# supply1.net
KiCad netlist of a schematic drawn in Altium Designer
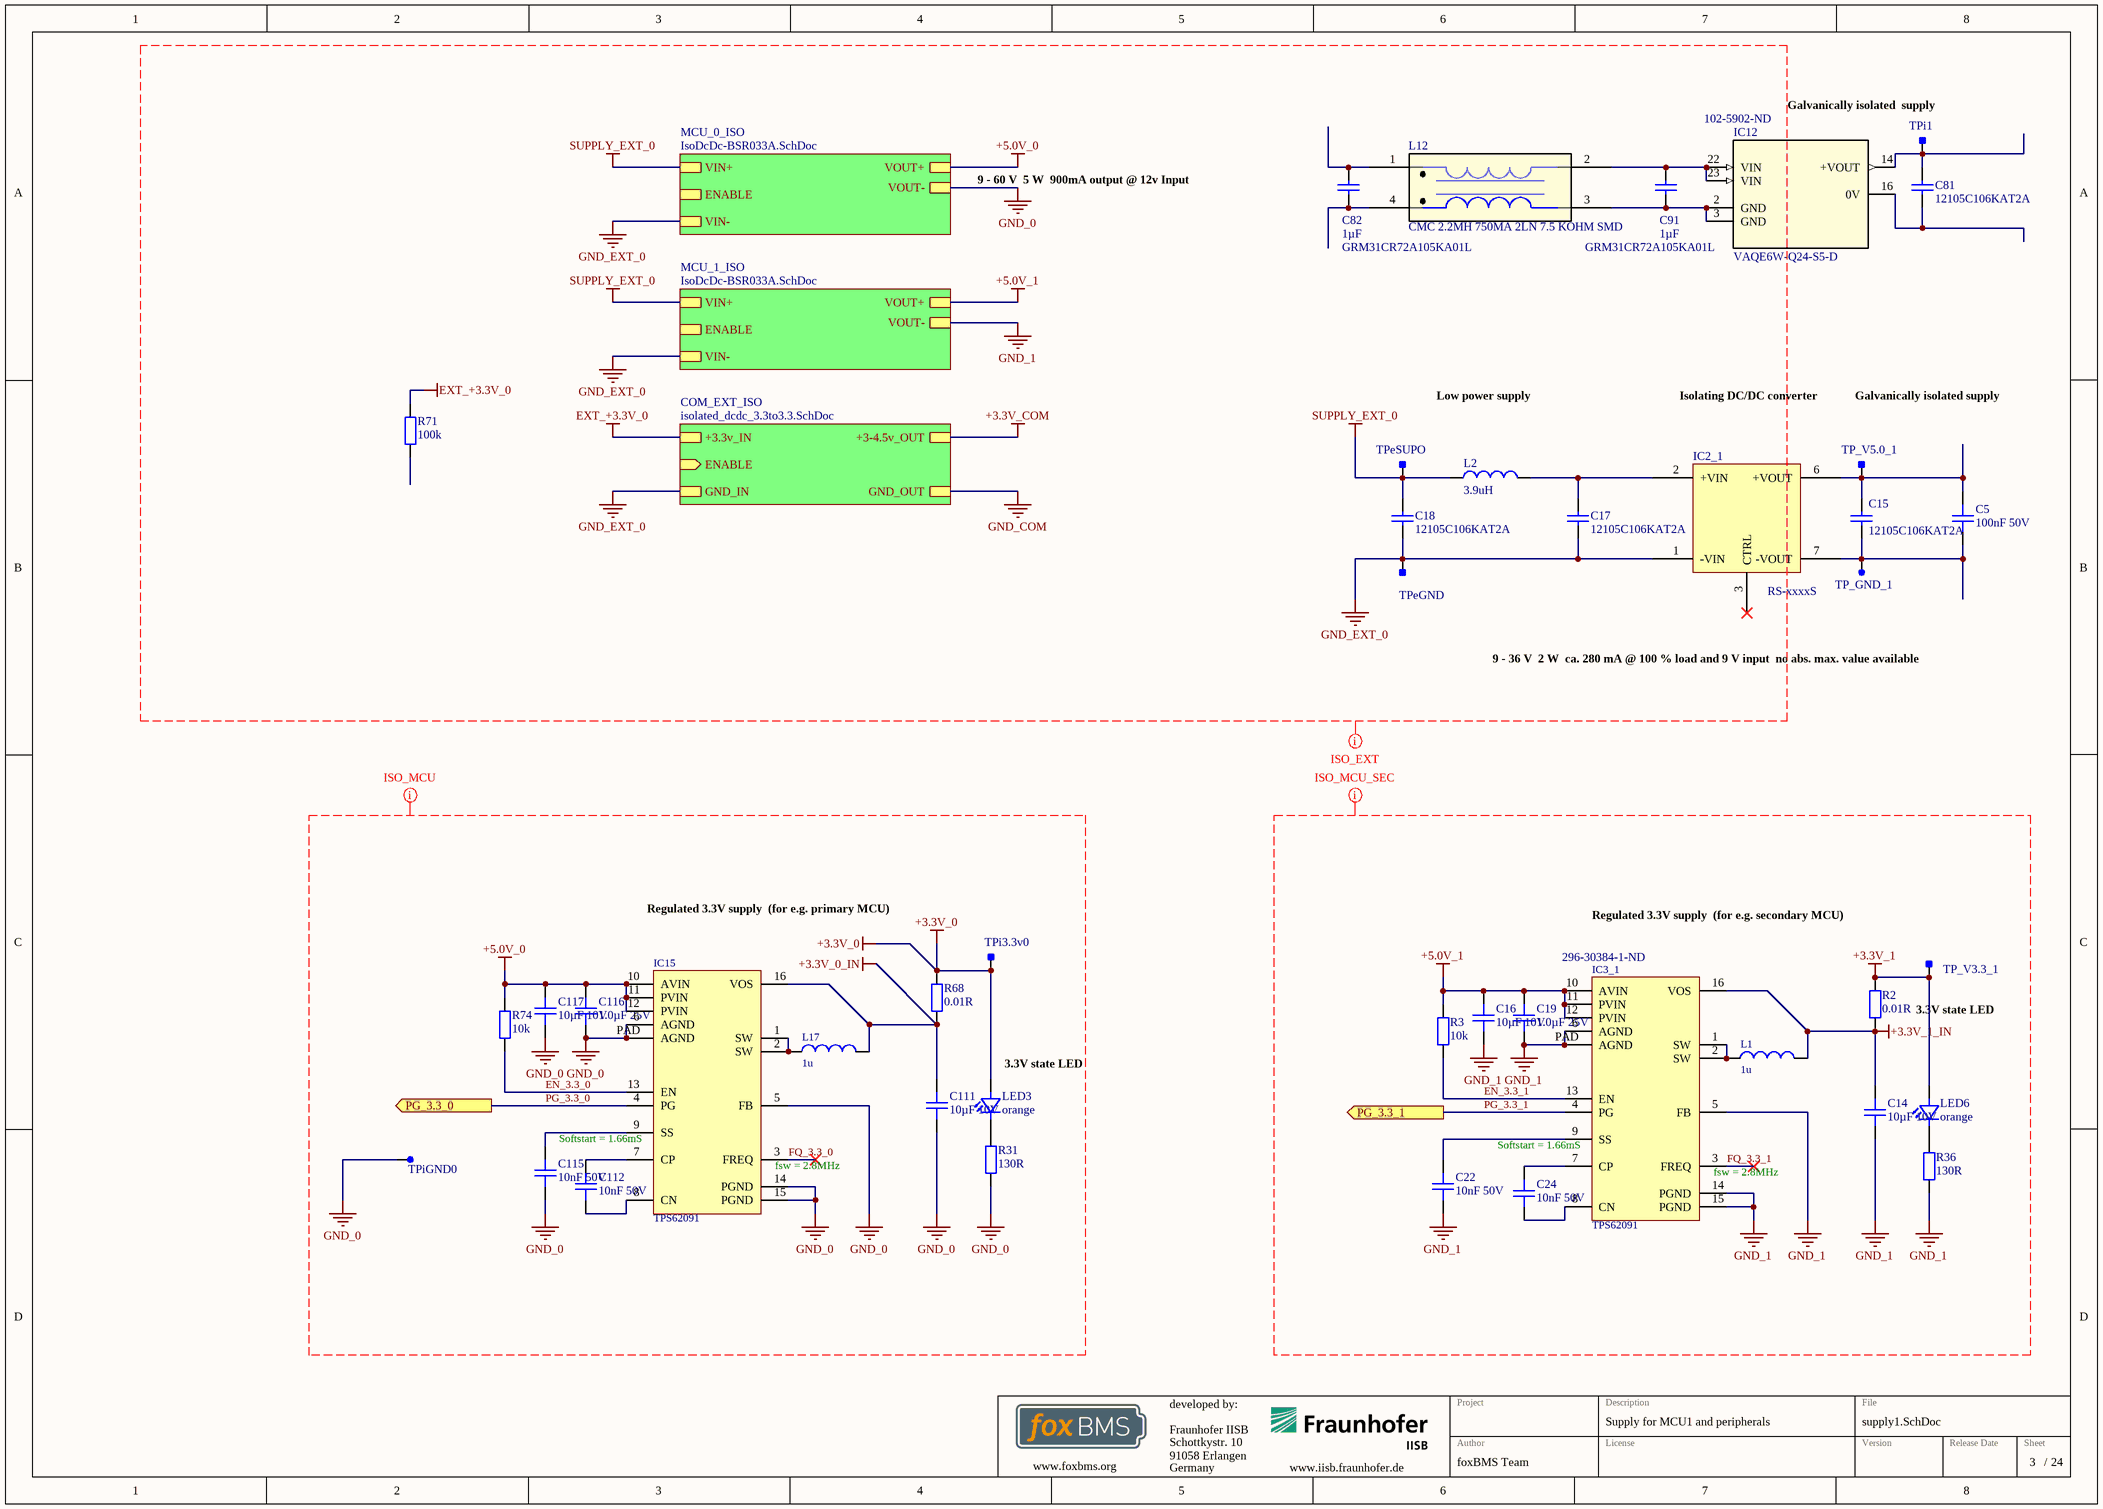
[diagram p0: supply1.SchDoc]

(export (version "E")
  (design (tool "Eeschema 10.0.6"))
  (components
    (comp (ref "C5")
      (value "100nF 50V")
      (footprint "0603C")
      (description "Ceramic, 100nF, ±10%, 50V, X7R, –55 to 125°C, 0603 (1608),RoHS, Automotive")
      (fields (field (name "PART NUMBER") "GCJ188R71H104KA12") (field (name "TOLERANCE") "±10%"))
      (libsource (lib "master-010106") (part "C"))
    )
    (comp (ref "C14")
      (value "10µF 10V")
      (footprint "0805C")
      (description "Ceramic, 10µF, ±10%, 10V, X7R, –55 to 125°C, 0805 (2012),RoHS, Automotive")
      (fields (field (name "PART NUMBER") "GCJ21BR71A106KE01") (field (name "TOLERANCE") "±10%"))
      (libsource (lib "master-010106") (part "gen_C_ceramic_10u_10V_X7R_0805"))
    )
    (comp (ref "C15")
      (value "12105C106KAT2A")
      (footprint "CAPC3225X279X50LL20T25")
      (description "Multilayer Ceramic Capacitor, 50 V, -55 to 125 degC, 2-Pin SMD (1210), RoHS, Tape and Reel")
      (fields (field (name "TOLERANCE") "10%") (field (name "MANUFACTURER") "AVX"))
      (libsource (lib "master-010106") (part "CAP-NP-2"))
    )
    (comp (ref "C16")
      (value "10µF 10V")
      (footprint "0805C")
      (description "Ceramic, 10µF, ±10%, 10V, X7R, –55 to 125°C, 0805 (2012),RoHS, Automotive")
      (fields (field (name "PART NUMBER") "GCJ21BR71A106KE01") (field (name "TOLERANCE") "±10%"))
      (libsource (lib "master-010106") (part "gen_C_ceramic_10u_10V_X7R_0805"))
    )
    (comp (ref "C17")
      (value "12105C106KAT2A")
      (footprint "CAPC3225X279X50LL20T25")
      (description "Multilayer Ceramic Capacitor, 50 V, -55 to 125 degC, 2-Pin SMD (1210), RoHS, Tape and Reel")
      (fields (field (name "TOLERANCE") "10%") (field (name "MANUFACTURER") "AVX"))
      (libsource (lib "master-010106") (part "CAP-NP-2"))
    )
    (comp (ref "C18")
      (value "12105C106KAT2A")
      (footprint "CAPC3225X279X50LL20T25")
      (description "Multilayer Ceramic Capacitor, 50 V, -55 to 125 degC, 2-Pin SMD (1210), RoHS, Tape and Reel")
      (fields (field (name "TOLERANCE") "10%") (field (name "MANUFACTURER") "AVX"))
      (libsource (lib "master-010106") (part "CAP-NP-2"))
    )
    (comp (ref "C19")
      (value "1.0µF 25V")
      (footprint "0603C")
      (description "Ceramic, 1.0µF, ±10%, 25V, X7R, –55 to 125°C, 0603 (1608),RoHS, Automotive")
      (fields (field (name "PART NUMBER") "GCJ188R71E105KA01") (field (name "TOLERANCE") "±10%"))
      (libsource (lib "master-010106") (part "gen_C_ceramic_1u_25V_X7R_0603"))
    )
    (comp (ref "C22")
      (value "10nF 50V")
      (footprint "0603C")
      (description "Ceramic, 10nF, ±10%, 50V, X7R, –55 to 125°C, 0603 (1608),RoHS, Automotive")
      (fields (field (name "PART NUMBER") "GCJ188R71H102KA01") (field (name "TOLERANCE") "±10%"))
      (libsource (lib "master-010106") (part "gen_C_ceramic_10n_50V_X7R_0603"))
    )
    (comp (ref "C24")
      (value "10nF 50V")
      (footprint "0603C")
      (description "Ceramic, 10nF, ±10%, 50V, X7R, –55 to 125°C, 0603 (1608),RoHS, Automotive")
      (fields (field (name "PART NUMBER") "GCJ188R71H102KA01") (field (name "TOLERANCE") "±10%"))
      (libsource (lib "master-010106") (part "gen_C_ceramic_10n_50V_X7R_0603"))
    )
    (comp (ref "C81")
      (value "12105C106KAT2A")
      (footprint "CAPC3225X279X50LL20T25")
      (description "Multilayer Ceramic Capacitor, 50 V, -55 to 125 degC, 2-Pin SMD (1210), RoHS, Tape and Reel")
      (fields (field (name "TOLERANCE") "10%") (field (name "MANUFACTURER") "AVX"))
      (libsource (lib "master-010106") (part "CAP-NP-2"))
    )
    (comp (ref "C82")
      (value "GRM31CR72A105KA01L")
      (footprint "CAPC3216X180X55ML20T25")
      (description "Chip Capacitor, 1 uF, +/- 10%, 100 V, -55 to 125 degC, 1206 (3216 Metric), RoHS, Tape and Reel")
      (fields
        (field (name "TOLERANCE") "±10%")
        (field (name "MANUFACTURER") "Murata")
        (field (name "CAPACITANCE") "1µF")
      )
      (libsource (lib "master-010106") (part "CAP-NP-2"))
    )
    (comp (ref "C91")
      (value "GRM31CR72A105KA01L")
      (footprint "CAPC3216X180X55ML20T25")
      (description "Chip Capacitor, 1 uF, +/- 10%, 100 V, -55 to 125 degC, 1206 (3216 Metric), RoHS, Tape and Reel")
      (fields
        (field (name "TOLERANCE") "±10%")
        (field (name "MANUFACTURER") "Murata")
        (field (name "CAPACITANCE") "1µF")
      )
      (libsource (lib "master-010106") (part "CAP-NP-2"))
    )
    (comp (ref "C111")
      (value "10µF 10V")
      (footprint "0805C")
      (description "Ceramic, 10µF, ±10%, 10V, X7R, –55 to 125°C, 0805 (2012),RoHS, Automotive")
      (fields (field (name "PART NUMBER") "GCJ21BR71A106KE01") (field (name "TOLERANCE") "±10%"))
      (libsource (lib "master-010106") (part "gen_C_ceramic_10u_10V_X7R_0805"))
    )
    (comp (ref "C112")
      (value "10nF 50V")
      (footprint "0603C")
      (description "Ceramic, 10nF, ±10%, 50V, X7R, –55 to 125°C, 0603 (1608),RoHS, Automotive")
      (fields (field (name "PART NUMBER") "GCJ188R71H102KA01") (field (name "TOLERANCE") "±10%"))
      (libsource (lib "master-010106") (part "gen_C_ceramic_10n_50V_X7R_0603"))
    )
    (comp (ref "C115")
      (value "10nF 50V")
      (footprint "0603C")
      (description "Ceramic, 10nF, ±10%, 50V, X7R, –55 to 125°C, 0603 (1608),RoHS, Automotive")
      (fields (field (name "PART NUMBER") "GCJ188R71H102KA01") (field (name "TOLERANCE") "±10%"))
      (libsource (lib "master-010106") (part "gen_C_ceramic_10n_50V_X7R_0603"))
    )
    (comp (ref "C116")
      (value "1.0µF 25V")
      (footprint "0603C")
      (description "Ceramic, 1.0µF, ±10%, 25V, X7R, –55 to 125°C, 0603 (1608),RoHS, Automotive")
      (fields (field (name "PART NUMBER") "GCJ188R71E105KA01") (field (name "TOLERANCE") "±10%"))
      (libsource (lib "master-010106") (part "gen_C_ceramic_1u_25V_X7R_0603"))
    )
    (comp (ref "C117")
      (value "10µF 10V")
      (footprint "0805C")
      (description "Ceramic, 10µF, ±10%, 10V, X7R, –55 to 125°C, 0805 (2012),RoHS, Automotive")
      (fields (field (name "PART NUMBER") "GCJ21BR71A106KE01") (field (name "TOLERANCE") "±10%"))
      (libsource (lib "master-010106") (part "gen_C_ceramic_10u_10V_X7R_0805"))
    )
    (comp (ref "IC2_1")
      (value "RS-xxxxS")
      (footprint "RECOM_RS-S_D")
      (description "Isolating DC/DC Converter")
      (fields (field (name "PART NUMBER") "Recom_RS-2405SZ/H3") (field (name "MANUFACTURER") "Recom"))
      (libsource (lib "OE750") (part "RS-xxxxS"))
    )
    (comp (ref "IC3_1")
      (value "TPS62091")
      (footprint "QFN-16-TI")
      (fields (field (name "SUPPLIER PART NUMBER 1") "296-30384-1-ND"))
      (libsource (lib "Schematic") (part "TPS62090"))
    )
    (comp (ref "IC12")
      (value "VAQE6W-Q24-S5-D")
      (footprint "VAQE6W-Q24-S5-D")
      (description "DC DC CONVERTER 5V 6W")
      (fields (field (name "POWER") "6W") (field (name "SUPPLIER PART NUMBER 1") "102-5902-ND"))
      (libsource (lib "ti-import") (part "VAQE6W-Q24-S5-D"))
    )
    (comp (ref "IC15")
      (value "TPS62091")
      (footprint "QFN-16-TI")
      (libsource (lib "Schematic") (part "TPS62090"))
    )
    (comp (ref "L1")
      (value "1u")
      (footprint "WE-LQS")
      (description "1u 3.8A 25mR 20% IFSC-1515 inductor, RoHS compliant")
      (fields (field (name "PART NUMBER") "IFSC-1515"))
      (libsource (lib "master-010106") (part "ind_1515"))
    )
    (comp (ref "L2")
      (value "3.9uH")
      (footprint "INDC4532")
      (description "3.9µH Unshielded Wirewound Inductor 1.32A 140mOhm Max 1812 (4532 Metric)")
      (fields
        (field (name "PARTNUMBER") "RLS-397")
        (field (name "PART NUMBER") "INDC-4532")
        (field (name "PUBLISHER") "Altium Limited")
      )
      (libsource (lib "Miscellaneous Devices") (part "Inductor"))
    )
    (comp (ref "L12")
      (value "CMC 2.2MH 750MA 2LN 7.5 KOHM SMD")
      (footprint "WE-SL5")
      (description "2.2mH @ 100kHz 2 Line Common Mode Choke Surface Mount 7.5 kOhms @ 4MHz 750mA DCR 300mOhm")
      (fields
        (field (name "MANUFACTURER_PART_NUMBER") "744272222")
        (field (name "MANUFACTURER") "Wurth Electronics Inc.")
        (field (name "COPYRIGHT") "Copyright (C) 2018 Accelerated Designs. All rights reserved")
      )
      (libsource (lib "ti-import") (part "744272222"))
    )
    (comp (ref "L17")
      (value "1u")
      (footprint "WE-LQS")
      (description "1u 3.8A 25mR 20% IFSC-1515 inductor, RoHS compliant")
      (fields (field (name "PART NUMBER") "IFSC-1515"))
      (libsource (lib "master-010106") (part "ind_1515"))
    )
    (comp (ref "LED3")
      (value "orange")
      (footprint "LEDC1608X07N")
      (description "LED")
      (fields (field (name "PART NUMBER") "gen_LED_0603_orange"))
      (libsource (lib "OE750") (part "D_LED"))
    )
    (comp (ref "LED6")
      (value "orange")
      (footprint "LEDC1608X07N")
      (description "LED")
      (fields (field (name "PART NUMBER") "gen_LED_0603_orange"))
      (libsource (lib "OE750") (part "D_LED"))
    )
    (comp (ref "R2")
      (value "0.01R")
      (footprint "0805R")
      (description "SMD Resistor 10m 0805")
      (fields (field (name "PART NUMBER") "gen_R_0.01R_0805"))
      (libsource (lib "master-010106") (part "gen_R_0.01R_0805"))
    )
    (comp (ref "R3")
      (value "10k")
      (footprint "0603R")
      (description "SMD Resistor 10k 0603")
      (fields (field (name "PART NUMBER") "gen_R_10k_0603") (field (name "TOLERANCE") "1%"))
      (libsource (lib "master-010106") (part "gen_R_10k_0603"))
    )
    (comp (ref "R31")
      (value "130R")
      (footprint "0603R")
      (description "SMD Resistor 130R 0603")
      (fields (field (name "PART NUMBER") "gen_R_130R_0603") (field (name "TOLERANCE") "1%"))
      (libsource (lib "master-010106") (part "R"))
    )
    (comp (ref "R36")
      (value "130R")
      (footprint "0603R")
      (description "SMD Resistor 130R 0603")
      (fields (field (name "PART NUMBER") "gen_R_130R_0603") (field (name "TOLERANCE") "1%"))
      (libsource (lib "master-010106") (part "R"))
    )
    (comp (ref "R68")
      (value "0.01R")
      (footprint "0805R")
      (description "SMD Resistor 10m 0805")
      (fields (field (name "PART NUMBER") "gen_R_0.01R_0805"))
      (libsource (lib "master-010106") (part "gen_R_0.01R_0805"))
    )
    (comp (ref "R71")
      (value "100k")
      (footprint "0603R")
      (description "SMD Resistor 100k 0603")
      (fields (field (name "PART NUMBER") "gen_R_100k_0603"))
      (libsource (lib "master-010106") (part "gen_R_100k_0603"))
    )
    (comp (ref "R74")
      (value "10k")
      (footprint "0603R")
      (description "SMD Resistor 10k 0603")
      (fields (field (name "PART NUMBER") "gen_R_10k_0603") (field (name "TOLERANCE") "1%"))
      (libsource (lib "master-010106") (part "gen_R_10k_0603"))
    )
    (comp (ref "TPeGND")
      (value "Testpoint_Square")
      (footprint "Testpoint_S1")
      (description "Testpoint, square")
      (libsource (lib "OE750") (part "Testpoint_Square"))
    )
    (comp (ref "TPeSUPO")
      (value "Testpoint_Square")
      (footprint "Testpoint_S1")
      (description "Testpoint, square")
      (libsource (lib "OE750") (part "Testpoint_Square"))
    )
    (comp (ref "TPi1")
      (value "Testpoint_Square")
      (footprint "Testpoint_S1")
      (description "Testpoint, square")
      (libsource (lib "OE750") (part "Testpoint_Square"))
    )
    (comp (ref "TPi3.3v0")
      (value "Testpoint_Square")
      (footprint "Testpoint_S1")
      (description "Testpoint, square")
      (libsource (lib "OE750") (part "Testpoint_Square"))
    )
    (comp (ref "TPiGND0")
      (value "Testpoint_Round")
      (footprint "Testpoint_D1V")
      (description "Testpoint, Via, round")
      (fields (field (name "PART NUMBER") "Testpoint_Round_Via"))
      (libsource (lib "OE750") (part "Testpoint_Round"))
    )
    (comp (ref "TP_GND_1")
      (value "Testpoint_Round")
      (footprint "Testpoint_D1V")
      (description "Testpoint, Via, round")
      (fields (field (name "PART NUMBER") "Testpoint_Round_Via"))
      (libsource (lib "OE750") (part "Testpoint_Round"))
    )
    (comp (ref "TP_V3.3_1")
      (value "Testpoint_Square")
      (footprint "Testpoint_S1")
      (description "Testpoint, square")
      (libsource (lib "OE750") (part "Testpoint_Square"))
    )
    (comp (ref "TP_V5.0_1")
      (value "Testpoint_Square")
      (footprint "Testpoint_S1")
      (description "Testpoint, square")
      (libsource (lib "OE750") (part "Testpoint_Square"))
    )
  )
  (nets
    (net (code "1") (name "+3.3V_0") (class "Default")
      (node (ref "LED3") (pin "2") (pinfunction "A_2") (pintype "passive"))
      (node (ref "R68") (pin "1") (pinfunction "1_1") (pintype "passive"))
      (node (ref "TPi3.3v0") (pin "1") (pinfunction "1_1") (pintype "passive"))
    )
    (net (code "2") (name "+3.3V_0_IN") (class "Default")
      (node (ref "C111") (pin "1") (pinfunction "1_1") (pintype "passive"))
      (node (ref "IC15") (pin "16") (pinfunction "VOS_16") (pintype "passive"))
      (node (ref "L17") (pin "2") (pinfunction "2_2") (pintype "passive"))
      (node (ref "R68") (pin "2") (pinfunction "2_2") (pintype "passive"))
    )
    (net (code "3") (name "+3.3V_1") (class "Default")
      (node (ref "LED6") (pin "2") (pinfunction "A_2") (pintype "passive"))
      (node (ref "R2") (pin "1") (pinfunction "1_1") (pintype "passive"))
      (node (ref "TP_V3.3_1") (pin "1") (pinfunction "1_1") (pintype "passive"))
    )
    (net (code "4") (name "+3.3V_1_IN") (class "Default")
      (node (ref "C14") (pin "1") (pinfunction "1_1") (pintype "passive"))
      (node (ref "IC3_1") (pin "16") (pinfunction "VOS_16") (pintype "passive"))
      (node (ref "L1") (pin "2") (pinfunction "2_2") (pintype "passive"))
      (node (ref "R2") (pin "2") (pinfunction "2_2") (pintype "passive"))
    )
    (net (code "6") (name "+5.0V_0") (class "Default")
      (node (ref "C116") (pin "1") (pinfunction "1_1") (pintype "passive"))
      (node (ref "C117") (pin "1") (pinfunction "1_1") (pintype "passive"))
      (node (ref "IC15") (pin "10") (pinfunction "AVIN_10") (pintype "passive"))
      (node (ref "IC15") (pin "11") (pinfunction "PVIN_11") (pintype "passive"))
      (node (ref "IC15") (pin "12") (pinfunction "PVIN_12") (pintype "passive"))
      (node (ref "R74") (pin "2") (pinfunction "2_2") (pintype "passive"))
    )
    (net (code "7") (name "+5.0V_1") (class "Default")
      (node (ref "C16") (pin "1") (pinfunction "1_1") (pintype "passive"))
      (node (ref "C19") (pin "1") (pinfunction "1_1") (pintype "passive"))
      (node (ref "IC3_1") (pin "10") (pinfunction "AVIN_10") (pintype "passive"))
      (node (ref "IC3_1") (pin "11") (pinfunction "PVIN_11") (pintype "passive"))
      (node (ref "IC3_1") (pin "12") (pinfunction "PVIN_12") (pintype "passive"))
      (node (ref "R3") (pin "2") (pinfunction "2_2") (pintype "passive"))
    )
    (net (code "11") (name "/EN_3.3_0") (class "Default")
      (node (ref "IC15") (pin "13") (pinfunction "EN_13") (pintype "passive"))
      (node (ref "R74") (pin "1") (pinfunction "1_1") (pintype "passive"))
    )
    (net (code "12") (name "/EN_3.3_1") (class "Default")
      (node (ref "IC3_1") (pin "13") (pinfunction "EN_13") (pintype "passive"))
      (node (ref "R3") (pin "1") (pinfunction "1_1") (pintype "passive"))
    )
    (net (code "13") (name "/FQ_3.3_0") (class "Default")
      (node (ref "IC15") (pin "3") (pinfunction "FREQ_3") (pintype "passive+no_connect"))
    )
    (net (code "14") (name "/FQ_3.3_1") (class "Default")
      (node (ref "IC3_1") (pin "3") (pinfunction "FREQ_3") (pintype "passive+no_connect"))
    )
    (net (code "15") (name "/PG_3.3_0") (class "Default")
      (node (ref "IC15") (pin "4") (pinfunction "PG_4") (pintype "passive"))
    )
    (net (code "16") (name "/PG_3.3_1") (class "Default")
      (node (ref "IC3_1") (pin "4") (pinfunction "PG_4") (pintype "passive"))
    )
    (net (code "17") (name "EXT_+3.3V_0") (class "Default")
      (node (ref "R71") (pin "2") (pinfunction "2_2") (pintype "passive"))
    )
    (net (code "18") (name "GND_0") (class "Default")
      (node (ref "C111") (pin "2") (pinfunction "2_2") (pintype "passive"))
      (node (ref "C115") (pin "2") (pinfunction "2_2") (pintype "passive"))
      (node (ref "C116") (pin "2") (pinfunction "2_2") (pintype "passive"))
      (node (ref "C117") (pin "2") (pinfunction "2_2") (pintype "passive"))
      (node (ref "IC15") (pin "14") (pinfunction "PGND_14") (pintype "passive"))
      (node (ref "IC15") (pin "15") (pinfunction "PGND_15") (pintype "passive"))
      (node (ref "IC15") (pin "5") (pinfunction "FB_5") (pintype "passive"))
      (node (ref "IC15") (pin "6") (pinfunction "AGND_6") (pintype "passive"))
      (node (ref "IC15") (pin "PAD") (pinfunction "AGND_PAD") (pintype "passive"))
      (node (ref "R31") (pin "1") (pinfunction "1_1") (pintype "passive"))
      (node (ref "TPiGND0") (pin "1") (pinfunction "1_1") (pintype "passive"))
    )
    (net (code "19") (name "GND_1") (class "Default")
      (node (ref "C14") (pin "2") (pinfunction "2_2") (pintype "passive"))
      (node (ref "C16") (pin "2") (pinfunction "2_2") (pintype "passive"))
      (node (ref "C19") (pin "2") (pinfunction "2_2") (pintype "passive"))
      (node (ref "C22") (pin "2") (pinfunction "2_2") (pintype "passive"))
      (node (ref "IC3_1") (pin "14") (pinfunction "PGND_14") (pintype "passive"))
      (node (ref "IC3_1") (pin "15") (pinfunction "PGND_15") (pintype "passive"))
      (node (ref "IC3_1") (pin "5") (pinfunction "FB_5") (pintype "passive"))
      (node (ref "IC3_1") (pin "6") (pinfunction "AGND_6") (pintype "passive"))
      (node (ref "IC3_1") (pin "PAD") (pinfunction "AGND_PAD") (pintype "passive"))
      (node (ref "R36") (pin "2") (pinfunction "2_2") (pintype "passive"))
    )
    (net (code "21") (name "GND_EXT_0") (class "Default")
      (node (ref "C17") (pin "1") (pinfunction "1_1") (pintype "passive"))
      (node (ref "C18") (pin "1") (pinfunction "1_1") (pintype "passive"))
      (node (ref "IC2_1") (pin "1") (pinfunction "-VIN_1") (pintype "power_in"))
      (node (ref "TPeGND") (pin "1") (pinfunction "1_1") (pintype "passive"))
    )
    (net (code "22") (name "Net-(C82-Pad1)") (class "Default")
      (node (ref "C82") (pin "1") (pinfunction "1_1") (pintype "passive"))
      (node (ref "L12") (pin "4") (pinfunction "4_4") (pintype "passive"))
    )
    (net (code "23") (name "Net-(C82-Pad2)") (class "Default")
      (node (ref "C82") (pin "2") (pinfunction "2_2") (pintype "passive"))
      (node (ref "L12") (pin "1") (pinfunction "1_1") (pintype "passive"))
    )
    (net (code "24") (name "Net-(C91-Pad1)") (class "Default")
      (node (ref "C91") (pin "1") (pinfunction "1_1") (pintype "passive"))
      (node (ref "IC12") (pin "2") (pinfunction "GND_2") (pintype "power_in"))
      (node (ref "IC12") (pin "3") (pinfunction "GND_3") (pintype "power_in"))
      (node (ref "L12") (pin "3") (pinfunction "3_3") (pintype "passive"))
    )
    (net (code "25") (name "Net-(C91-Pad2)") (class "Default")
      (node (ref "C91") (pin "2") (pinfunction "2_2") (pintype "passive"))
      (node (ref "IC12") (pin "22") (pinfunction "VIN_22") (pintype "input"))
      (node (ref "IC12") (pin "23") (pinfunction "VIN_23") (pintype "input"))
      (node (ref "L12") (pin "2") (pinfunction "2_2") (pintype "passive"))
    )
    (net (code "26") (name "Net-(IC2_1-+VIN)") (class "Default")
      (node (ref "C17") (pin "2") (pinfunction "2_2") (pintype "passive"))
      (node (ref "IC2_1") (pin "2") (pinfunction "+VIN_2") (pintype "power_in"))
      (node (ref "L2") (pin "2") (pinfunction "2_2") (pintype "passive"))
    )
    (net (code "27") (name "Net-(IC2_1-+VOUT)") (class "Default")
      (node (ref "C15") (pin "2") (pinfunction "2_2") (pintype "passive"))
      (node (ref "C5") (pin "1") (pinfunction "1_1") (pintype "passive"))
      (node (ref "IC2_1") (pin "6") (pinfunction "+VOUT_6") (pintype "power_in"))
      (node (ref "TP_V5.0_1") (pin "1") (pinfunction "1_1") (pintype "passive"))
    )
    (net (code "28") (name "Net-(IC2_1--VOUT)") (class "Default")
      (node (ref "C15") (pin "1") (pinfunction "1_1") (pintype "passive"))
      (node (ref "C5") (pin "2") (pinfunction "2_2") (pintype "passive"))
      (node (ref "IC2_1") (pin "7") (pinfunction "-VOUT_7") (pintype "power_in"))
      (node (ref "TP_GND_1") (pin "1") (pinfunction "1_1") (pintype "passive"))
    )
    (net (code "29") (name "Net-(IC3_1-CN)") (class "Default")
      (node (ref "C24") (pin "2") (pinfunction "2_2") (pintype "passive"))
      (node (ref "IC3_1") (pin "8") (pinfunction "CN_8") (pintype "passive"))
    )
    (net (code "30") (name "Net-(IC3_1-CP)") (class "Default")
      (node (ref "C24") (pin "1") (pinfunction "1_1") (pintype "passive"))
      (node (ref "IC3_1") (pin "7") (pinfunction "CP_7") (pintype "passive"))
    )
    (net (code "31") (name "Net-(IC3_1-SS)") (class "Default")
      (node (ref "C22") (pin "1") (pinfunction "1_1") (pintype "passive"))
      (node (ref "IC3_1") (pin "9") (pinfunction "SS_9") (pintype "passive"))
    )
    (net (code "32") (name "Net-(IC3_1-SW-Pad1)") (class "Default")
      (node (ref "IC3_1") (pin "1") (pinfunction "SW_1") (pintype "passive"))
      (node (ref "IC3_1") (pin "2") (pinfunction "SW_2") (pintype "passive"))
      (node (ref "L1") (pin "1") (pinfunction "1_1") (pintype "passive"))
    )
    (net (code "33") (name "Net-(IC12-+VOUT)") (class "Default")
      (node (ref "C81") (pin "2") (pinfunction "2_2") (pintype "passive"))
      (node (ref "IC12") (pin "14") (pinfunction "+VOUT_14") (pintype "output"))
      (node (ref "TPi1") (pin "1") (pinfunction "1_1") (pintype "passive"))
    )
    (net (code "34") (name "Net-(IC12-0V)") (class "Default")
      (node (ref "C81") (pin "1") (pinfunction "1_1") (pintype "passive"))
      (node (ref "IC12") (pin "16") (pinfunction "0V_16") (pintype "power_in"))
    )
    (net (code "35") (name "Net-(IC15-CN)") (class "Default")
      (node (ref "C112") (pin "2") (pinfunction "2_2") (pintype "passive"))
      (node (ref "IC15") (pin "8") (pinfunction "CN_8") (pintype "passive"))
    )
    (net (code "36") (name "Net-(IC15-CP)") (class "Default")
      (node (ref "C112") (pin "1") (pinfunction "1_1") (pintype "passive"))
      (node (ref "IC15") (pin "7") (pinfunction "CP_7") (pintype "passive"))
    )
    (net (code "37") (name "Net-(IC15-SS)") (class "Default")
      (node (ref "C115") (pin "1") (pinfunction "1_1") (pintype "passive"))
      (node (ref "IC15") (pin "9") (pinfunction "SS_9") (pintype "passive"))
    )
    (net (code "38") (name "Net-(IC15-SW-Pad1)") (class "Default")
      (node (ref "IC15") (pin "1") (pinfunction "SW_1") (pintype "passive"))
      (node (ref "IC15") (pin "2") (pinfunction "SW_2") (pintype "passive"))
      (node (ref "L17") (pin "1") (pinfunction "1_1") (pintype "passive"))
    )
    (net (code "39") (name "Net-(LED3-C)") (class "Default")
      (node (ref "LED3") (pin "1") (pinfunction "C_1") (pintype "passive"))
      (node (ref "R31") (pin "2") (pinfunction "2_2") (pintype "passive"))
    )
    (net (code "40") (name "Net-(LED6-C)") (class "Default")
      (node (ref "LED6") (pin "1") (pinfunction "C_1") (pintype "passive"))
      (node (ref "R36") (pin "1") (pinfunction "1_1") (pintype "passive"))
    )
    (net (code "41") (name "SUPPLY_EXT_0") (class "Default")
      (node (ref "C18") (pin "2") (pinfunction "2_2") (pintype "passive"))
      (node (ref "L2") (pin "1") (pinfunction "1_1") (pintype "passive"))
      (node (ref "TPeSUPO") (pin "1") (pinfunction "1_1") (pintype "passive"))
    )
    (net (code "42") (name "unconnected-(IC2_1-CTRL-Pad3)") (class "Default")
      (node (ref "IC2_1") (pin "3") (pinfunction "CTRL_3") (pintype "passive+no_connect"))
    )
    (net (code "43") (name "unconnected-(R71-Pad1)") (class "Default")
      (node (ref "R71") (pin "1") (pinfunction "1_1") (pintype "passive"))
    )
  )
)
